# mcu_core.net
KiCad netlist of a schematic drawn in Altium Designer
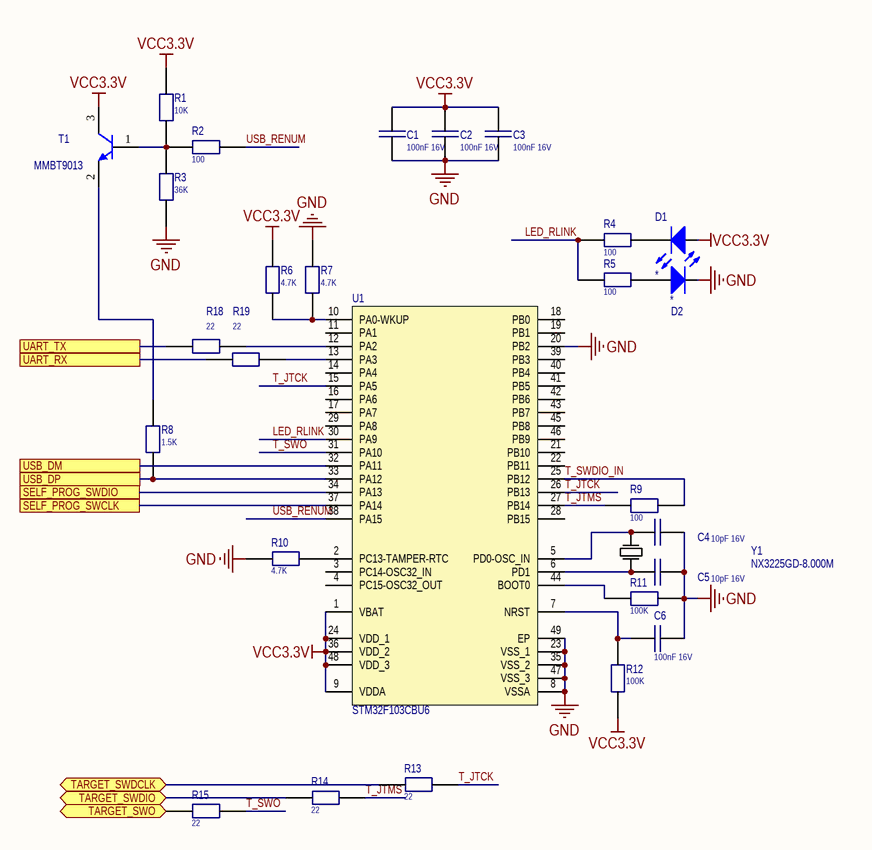
[diagram p0: mcu_core.schdoc]

(export (version "E")
  (design (tool "Eeschema 10.0.6"))
  (components
    (comp (ref "C1")
      (value "100nF 16V")
      (footprint "C_0402")
      (description "Capacitor")
      (libsource (lib "capacitors") (part "C0402"))
    )
    (comp (ref "C2")
      (value "100nF 16V")
      (footprint "C_0402")
      (description "Capacitor")
      (libsource (lib "capacitors") (part "C0402"))
    )
    (comp (ref "C3")
      (value "100nF 16V")
      (footprint "C_0402")
      (description "Capacitor")
      (libsource (lib "capacitors") (part "C0402"))
    )
    (comp (ref "C4")
      (value "10pF 16V")
      (footprint "C_0402")
      (description "Capacitor")
      (libsource (lib "capacitors") (part "C0402"))
    )
    (comp (ref "C5")
      (value "10pF 16V")
      (footprint "C_0402")
      (description "Capacitor")
      (libsource (lib "capacitors") (part "C0402"))
    )
    (comp (ref "C6")
      (value "100nF 16V")
      (footprint "C_0402")
      (description "Capacitor")
      (libsource (lib "capacitors") (part "C0402"))
    )
    (comp (ref "D1")
      (value "*")
      (footprint "led_lcd:LED_1206")
      (description "Typical INFRARED GaAs LED")
      (libsource (lib "led_lcd") (part "LED_SMT_1206"))
    )
    (comp (ref "D2")
      (value "*")
      (footprint "LED_1206")
      (description "Typical INFRARED GaAs LED")
      (libsource (lib "led_lcd") (part "LED_SMT_1206"))
    )
    (comp (ref "R1")
      (value "10K")
      (footprint "R_0402")
      (description "Resistor")
      (libsource (lib "resistors") (part "R0402"))
    )
    (comp (ref "R2")
      (value "100")
      (footprint "R_0402")
      (description "Resistor")
      (libsource (lib "resistors") (part "R0402"))
    )
    (comp (ref "R3")
      (value "36K")
      (footprint "R_0402")
      (description "Resistor")
      (libsource (lib "resistors") (part "R0402"))
    )
    (comp (ref "R4")
      (value "100")
      (footprint "R_0402")
      (description "Resistor")
      (libsource (lib "resistors") (part "R0402"))
    )
    (comp (ref "R5")
      (value "100")
      (footprint "R_0402")
      (description "Resistor")
      (libsource (lib "resistors") (part "R0402"))
    )
    (comp (ref "R6")
      (value "4.7K")
      (footprint "R_0402")
      (description "Resistor")
      (libsource (lib "resistors") (part "R0402"))
    )
    (comp (ref "R7")
      (value "4.7K")
      (footprint "R_0402")
      (description "Resistor")
      (libsource (lib "resistors") (part "R0402"))
    )
    (comp (ref "R8")
      (value "1.5K")
      (footprint "R_0402")
      (description "Resistor")
      (libsource (lib "resistors") (part "R0402"))
    )
    (comp (ref "R9")
      (value "100")
      (footprint "R_0402")
      (description "Resistor")
      (libsource (lib "resistors") (part "R0402"))
    )
    (comp (ref "R10")
      (value "4.7K")
      (footprint "R_0402")
      (description "Resistor")
      (libsource (lib "resistors") (part "R0402"))
    )
    (comp (ref "R11")
      (value "100K")
      (footprint "R_0402")
      (description "Resistor")
      (libsource (lib "resistors") (part "R0402"))
    )
    (comp (ref "R12")
      (value "100K")
      (footprint "R_0402")
      (description "Resistor")
      (libsource (lib "resistors") (part "R0402"))
    )
    (comp (ref "R13")
      (value "22")
      (footprint "R_0402")
      (description "Resistor")
      (libsource (lib "resistors") (part "R0402"))
    )
    (comp (ref "R14")
      (value "22")
      (footprint "R_0402")
      (description "Resistor")
      (libsource (lib "resistors") (part "R0402"))
    )
    (comp (ref "R15")
      (value "22")
      (footprint "R_0402")
      (description "Resistor")
      (libsource (lib "resistors") (part "R0402"))
    )
    (comp (ref "R18")
      (value "22")
      (footprint "R_0402")
      (description "Resistor")
      (libsource (lib "resistors") (part "R0402"))
    )
    (comp (ref "R19")
      (value "22")
      (footprint "R_0402")
      (description "Resistor")
      (libsource (lib "resistors") (part "R0402"))
    )
    (comp (ref "T1")
      (value "MMBT9013")
      (footprint "SOT23")
      (description "NPN Bipolar Transistor")
      (fields (field (name "PUBLISHER") "Altium Limited"))
      (libsource (lib "MB1167") (part "NPN"))
    )
    (comp (ref "U1")
      (value "STM32F103CBU6")
      (footprint "STM-UFQFPN48_M")
      (libsource (lib "AX_Altium_v2.3") (part "STM32F103CBU6"))
    )
    (comp (ref "Y1")
      (value "NX3225GD-8.000M")
      (footprint "NX3225GD")
      (description "Crystal Oscillator")
      (libsource (lib "crystals_oscillators") (part "NX3225GD"))
    )
  )
  (nets
    (net (code "1") (name "/LED_RLINK") (class "Default")
      (node (ref "R4") (pin "2") (pinfunction "2_2") (pintype "passive"))
      (node (ref "R5") (pin "2") (pinfunction "2_2") (pintype "passive"))
      (node (ref "U1") (pin "30") (pinfunction "PA9_30") (pintype "passive"))
    )
    (net (code "2") (name "/SELF_PROG_SWCLK") (class "Default")
      (node (ref "U1") (pin "37") (pinfunction "PA14_37") (pintype "passive"))
    )
    (net (code "3") (name "/SELF_PROG_SWDIO") (class "Default")
      (node (ref "U1") (pin "34") (pinfunction "PA13_34") (pintype "passive"))
    )
    (net (code "4") (name "/TARGET_SWDCLK") (class "Default")
      (node (ref "R13") (pin "2") (pinfunction "2_2") (pintype "passive"))
    )
    (net (code "5") (name "/TARGET_SWDIO") (class "Default")
      (node (ref "R14") (pin "2") (pinfunction "2_2") (pintype "passive"))
    )
    (net (code "6") (name "/TARGET_SWO") (class "Default")
      (node (ref "R15") (pin "2") (pinfunction "2_2") (pintype "passive"))
    )
    (net (code "7") (name "/T_JTCK") (class "Default")
      (node (ref "R13") (pin "1") (pinfunction "1_1") (pintype "passive"))
      (node (ref "U1") (pin "15") (pinfunction "PA5_15") (pintype "passive"))
      (node (ref "U1") (pin "26") (pinfunction "PB13_26") (pintype "passive"))
    )
    (net (code "8") (name "/T_JTMS") (class "Default")
      (node (ref "R14") (pin "1") (pinfunction "1_1") (pintype "passive"))
      (node (ref "R9") (pin "2") (pinfunction "2_2") (pintype "passive"))
      (node (ref "U1") (pin "27") (pinfunction "PB14_27") (pintype "passive"))
    )
    (net (code "9") (name "/T_SWDIO_IN") (class "Default")
      (node (ref "R9") (pin "1") (pinfunction "1_1") (pintype "passive"))
      (node (ref "U1") (pin "25") (pinfunction "PB12_25") (pintype "passive"))
    )
    (net (code "10") (name "/T_SWO") (class "Default")
      (node (ref "R15") (pin "1") (pinfunction "1_1") (pintype "passive"))
      (node (ref "U1") (pin "31") (pinfunction "PA10_31") (pintype "passive"))
    )
    (net (code "11") (name "/UART_RX") (class "Default")
      (node (ref "R19") (pin "2") (pinfunction "2_2") (pintype "passive"))
    )
    (net (code "12") (name "/UART_TX") (class "Default")
      (node (ref "R18") (pin "2") (pinfunction "2_2") (pintype "passive"))
    )
    (net (code "13") (name "/USB_DM") (class "Default")
      (node (ref "U1") (pin "32") (pinfunction "PA11_32") (pintype "passive"))
    )
    (net (code "14") (name "/USB_DP") (class "Default")
      (node (ref "R8") (pin "1") (pinfunction "1_1") (pintype "passive"))
      (node (ref "U1") (pin "33") (pinfunction "PA12_33") (pintype "passive"))
    )
    (net (code "15") (name "/USB_RENUM") (class "Default")
      (node (ref "R2") (pin "1") (pinfunction "1_1") (pintype "passive"))
      (node (ref "U1") (pin "38") (pinfunction "PA15_38") (pintype "passive"))
    )
    (net (code "16") (name "GND") (class "Default")
      (node (ref "C1") (pin "1") (pinfunction "1_1") (pintype "passive"))
      (node (ref "C2") (pin "1") (pinfunction "1_1") (pintype "passive"))
      (node (ref "C3") (pin "1") (pinfunction "1_1") (pintype "passive"))
      (node (ref "C4") (pin "1") (pinfunction "1_1") (pintype "passive"))
      (node (ref "C5") (pin "1") (pinfunction "1_1") (pintype "passive"))
      (node (ref "C6") (pin "1") (pinfunction "1_1") (pintype "passive"))
      (node (ref "D2") (pin "2") (pinfunction "K_2") (pintype "passive"))
      (node (ref "R10") (pin "2") (pinfunction "2_2") (pintype "passive"))
      (node (ref "R11") (pin "1") (pinfunction "1_1") (pintype "passive"))
      (node (ref "R3") (pin "2") (pinfunction "2_2") (pintype "passive"))
      (node (ref "R7") (pin "2") (pinfunction "2_2") (pintype "passive"))
      (node (ref "U1") (pin "20") (pinfunction "PB2_20") (pintype "passive"))
      (node (ref "U1") (pin "23") (pinfunction "VSS_1_23") (pintype "passive"))
      (node (ref "U1") (pin "35") (pinfunction "VSS_2_35") (pintype "passive"))
      (node (ref "U1") (pin "47") (pinfunction "VSS_3_47") (pintype "passive"))
      (node (ref "U1") (pin "49") (pinfunction "EP_49") (pintype "passive"))
      (node (ref "U1") (pin "8") (pinfunction "VSSA_8") (pintype "passive"))
    )
    (net (code "17") (name "Net-(D1-K)") (class "Default")
      (node (ref "D1") (pin "2") (pinfunction "K_2") (pintype "passive"))
      (node (ref "R4") (pin "1") (pinfunction "1_1") (pintype "passive"))
    )
    (net (code "18") (name "Net-(D2-A)") (class "Default")
      (node (ref "D2") (pin "1") (pinfunction "A_1") (pintype "passive"))
      (node (ref "R5") (pin "1") (pinfunction "1_1") (pintype "passive"))
    )
    (net (code "19") (name "Net-(T1-B)") (class "Default")
      (node (ref "R1") (pin "1") (pinfunction "1_1") (pintype "passive"))
      (node (ref "R2") (pin "2") (pinfunction "2_2") (pintype "passive"))
      (node (ref "R3") (pin "1") (pinfunction "1_1") (pintype "passive"))
      (node (ref "T1") (pin "1") (pinfunction "B_1") (pintype "passive"))
    )
    (net (code "20") (name "Net-(T1-E)") (class "Default")
      (node (ref "R8") (pin "2") (pinfunction "2_2") (pintype "passive"))
      (node (ref "T1") (pin "2") (pinfunction "E_2") (pintype "passive"))
    )
    (net (code "21") (name "Net-(U1-BOOT0)") (class "Default")
      (node (ref "R11") (pin "2") (pinfunction "2_2") (pintype "passive"))
      (node (ref "U1") (pin "44") (pinfunction "BOOT0_44") (pintype "passive"))
    )
    (net (code "22") (name "Net-(U1-NRST)") (class "Default")
      (node (ref "C6") (pin "2") (pinfunction "2_2") (pintype "passive"))
      (node (ref "R12") (pin "1") (pinfunction "1_1") (pintype "passive"))
      (node (ref "U1") (pin "7") (pinfunction "NRST_7") (pintype "passive"))
    )
    (net (code "23") (name "Net-(U1-PA0-WKUP)") (class "Default")
      (node (ref "R6") (pin "1") (pinfunction "1_1") (pintype "passive"))
      (node (ref "R7") (pin "1") (pinfunction "1_1") (pintype "passive"))
      (node (ref "U1") (pin "10") (pinfunction "PA0-WKUP_10") (pintype "passive"))
    )
    (net (code "24") (name "Net-(U1-PA2)") (class "Default")
      (node (ref "R18") (pin "1") (pinfunction "1_1") (pintype "passive"))
      (node (ref "U1") (pin "12") (pinfunction "PA2_12") (pintype "passive"))
    )
    (net (code "25") (name "Net-(U1-PA3)") (class "Default")
      (node (ref "R19") (pin "1") (pinfunction "1_1") (pintype "passive"))
      (node (ref "U1") (pin "13") (pinfunction "PA3_13") (pintype "passive"))
    )
    (net (code "26") (name "Net-(U1-PC13-TAMPER-RTC)") (class "Default")
      (node (ref "R10") (pin "1") (pinfunction "1_1") (pintype "passive"))
      (node (ref "U1") (pin "2") (pinfunction "PC13-TAMPER-RTC_2") (pintype "passive"))
    )
    (net (code "27") (name "Net-(U1-PD0-OSC_IN)") (class "Default")
      (node (ref "C4") (pin "2") (pinfunction "2_2") (pintype "passive"))
      (node (ref "U1") (pin "5") (pinfunction "PD0-OSC_IN_5") (pintype "passive"))
      (node (ref "Y1") (pin "2") (pinfunction "OSC2_2") (pintype "passive"))
    )
    (net (code "28") (name "Net-(U1-PD1)") (class "Default")
      (node (ref "C5") (pin "2") (pinfunction "2_2") (pintype "passive"))
      (node (ref "U1") (pin "6") (pinfunction "PD1_6") (pintype "passive"))
      (node (ref "Y1") (pin "1") (pinfunction "OSC1_1") (pintype "passive"))
    )
    (net (code "29") (name "VCC3.3V") (class "Default")
      (node (ref "C1") (pin "2") (pinfunction "2_2") (pintype "passive"))
      (node (ref "C2") (pin "2") (pinfunction "2_2") (pintype "passive"))
      (node (ref "C3") (pin "2") (pinfunction "2_2") (pintype "passive"))
      (node (ref "D1") (pin "1") (pinfunction "A_1") (pintype "passive"))
      (node (ref "R1") (pin "2") (pinfunction "2_2") (pintype "passive"))
      (node (ref "R12") (pin "2") (pinfunction "2_2") (pintype "passive"))
      (node (ref "R6") (pin "2") (pinfunction "2_2") (pintype "passive"))
      (node (ref "T1") (pin "3") (pinfunction "C_3") (pintype "passive"))
      (node (ref "U1") (pin "1") (pinfunction "VBAT_1") (pintype "passive"))
      (node (ref "U1") (pin "24") (pinfunction "VDD_1_24") (pintype "passive"))
      (node (ref "U1") (pin "36") (pinfunction "VDD_2_36") (pintype "passive"))
      (node (ref "U1") (pin "48") (pinfunction "VDD_3_48") (pintype "passive"))
      (node (ref "U1") (pin "9") (pinfunction "VDDA_9") (pintype "passive"))
    )
    (net (code "30") (name "unconnected-(U1-PA1-Pad11)") (class "Default")
      (node (ref "U1") (pin "11") (pinfunction "PA1_11") (pintype "passive"))
    )
    (net (code "31") (name "unconnected-(U1-PA4-Pad14)") (class "Default")
      (node (ref "U1") (pin "14") (pinfunction "PA4_14") (pintype "passive"))
    )
    (net (code "32") (name "unconnected-(U1-PA6-Pad16)") (class "Default")
      (node (ref "U1") (pin "16") (pinfunction "PA6_16") (pintype "passive"))
    )
    (net (code "33") (name "unconnected-(U1-PA7-Pad17)") (class "Default")
      (node (ref "U1") (pin "17") (pinfunction "PA7_17") (pintype "passive"))
    )
    (net (code "34") (name "unconnected-(U1-PA8-Pad29)") (class "Default")
      (node (ref "U1") (pin "29") (pinfunction "PA8_29") (pintype "passive"))
    )
    (net (code "35") (name "unconnected-(U1-PB0-Pad18)") (class "Default")
      (node (ref "U1") (pin "18") (pinfunction "PB0_18") (pintype "passive"))
    )
    (net (code "36") (name "unconnected-(U1-PB1-Pad19)") (class "Default")
      (node (ref "U1") (pin "19") (pinfunction "PB1_19") (pintype "passive"))
    )
    (net (code "37") (name "unconnected-(U1-PB3-Pad39)") (class "Default")
      (node (ref "U1") (pin "39") (pinfunction "PB3_39") (pintype "passive"))
    )
    (net (code "38") (name "unconnected-(U1-PB4-Pad40)") (class "Default")
      (node (ref "U1") (pin "40") (pinfunction "PB4_40") (pintype "passive"))
    )
    (net (code "39") (name "unconnected-(U1-PB5-Pad41)") (class "Default")
      (node (ref "U1") (pin "41") (pinfunction "PB5_41") (pintype "passive"))
    )
    (net (code "40") (name "unconnected-(U1-PB6-Pad42)") (class "Default")
      (node (ref "U1") (pin "42") (pinfunction "PB6_42") (pintype "passive"))
    )
    (net (code "41") (name "unconnected-(U1-PB7-Pad43)") (class "Default")
      (node (ref "U1") (pin "43") (pinfunction "PB7_43") (pintype "passive"))
    )
    (net (code "42") (name "unconnected-(U1-PB8-Pad45)") (class "Default")
      (node (ref "U1") (pin "45") (pinfunction "PB8_45") (pintype "passive"))
    )
    (net (code "43") (name "unconnected-(U1-PB9-Pad46)") (class "Default")
      (node (ref "U1") (pin "46") (pinfunction "PB9_46") (pintype "passive"))
    )
    (net (code "44") (name "unconnected-(U1-PB10-Pad21)") (class "Default")
      (node (ref "U1") (pin "21") (pinfunction "PB10_21") (pintype "passive"))
    )
    (net (code "45") (name "unconnected-(U1-PB11-Pad22)") (class "Default")
      (node (ref "U1") (pin "22") (pinfunction "PB11_22") (pintype "passive"))
    )
    (net (code "46") (name "unconnected-(U1-PB15-Pad28)") (class "Default")
      (node (ref "U1") (pin "28") (pinfunction "PB15_28") (pintype "passive"))
    )
    (net (code "47") (name "unconnected-(U1-PC14-OSC32_IN-Pad3)") (class "Default")
      (node (ref "U1") (pin "3") (pinfunction "PC14-OSC32_IN_3") (pintype "passive"))
    )
    (net (code "48") (name "unconnected-(U1-PC15-OSC32_OUT-Pad4)") (class "Default")
      (node (ref "U1") (pin "4") (pinfunction "PC15-OSC32_OUT_4") (pintype "passive"))
    )
  )
)
